# md_ver10_6.net
KiCad netlist of a schematic drawn in EAGLE
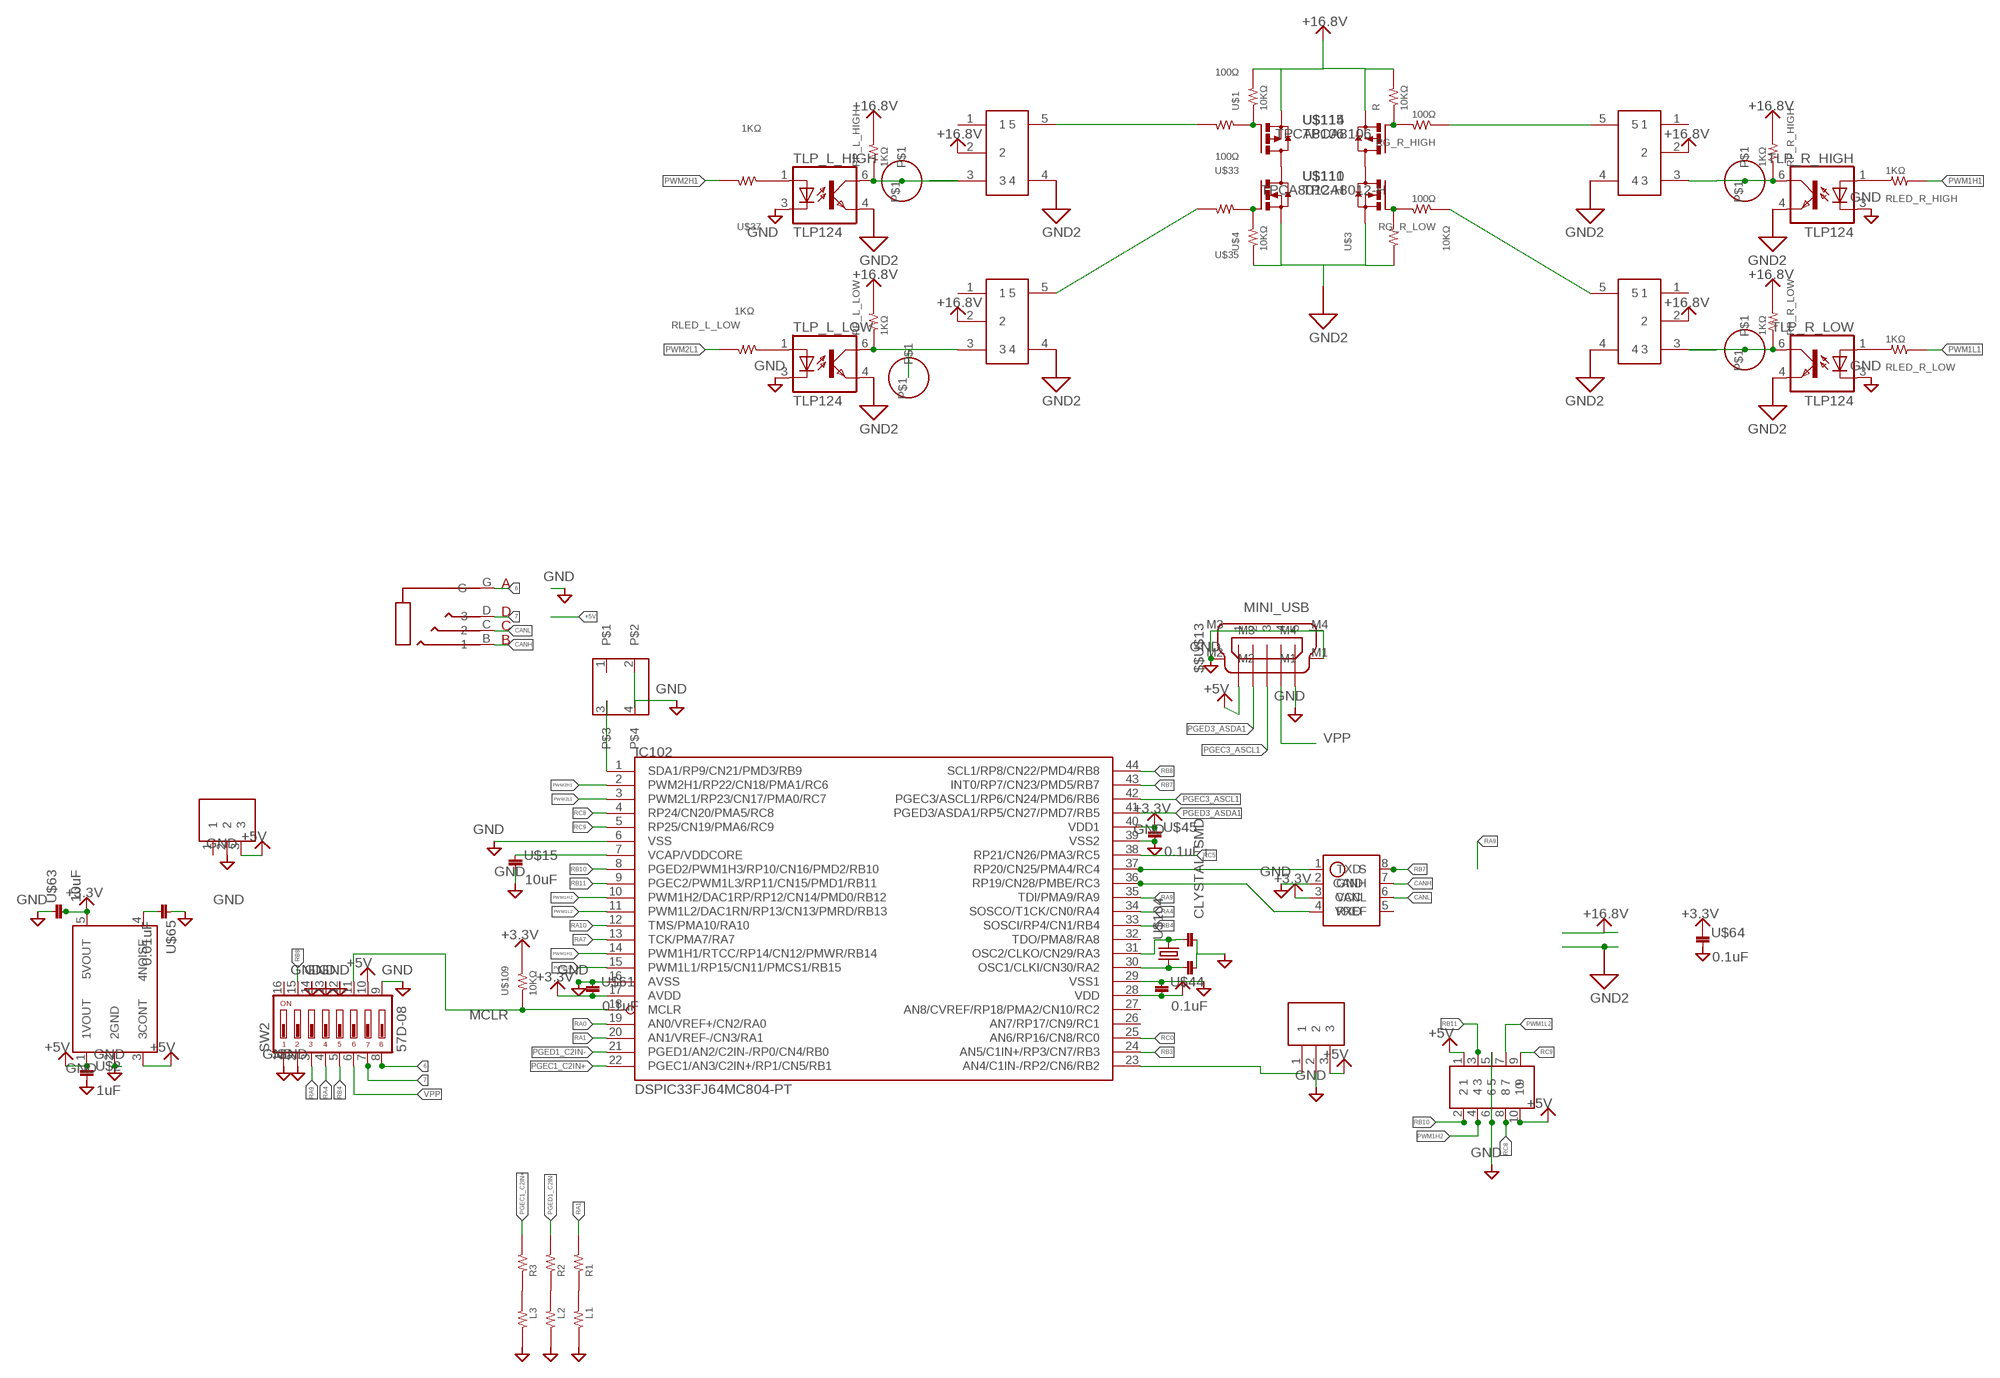
[diagram p0: schematic, sheet 1]

(export (version "E")
  (design (tool "Eeschema 10.0.6"))
  (components
    (comp (ref "$$U$5")
      (value "PAD1_4MM")
      (footprint "eagle-import:PAD1_4MM")
      (libsource (lib "eagle-import") (part "PAD1_4MM"))
    )
    (comp (ref "$$U$6")
      (value "PAD1_4MM")
      (footprint "eagle-import:PAD1_4MM")
      (libsource (lib "eagle-import") (part "PAD1_4MM"))
    )
    (comp (ref "$$U$13")
      (value "MINI_USB")
      (footprint "eagle-import:MINI_USB")
      (libsource (lib "eagle-import") (part "MINI_USB"))
    )
    (comp (ref "$$U$14")
      (value "AUDIO4")
      (footprint "eagle-import:AUDIO4_MJ")
      (libsource (lib "eagle-import") (part "AUDIO4"))
    )
    (comp (ref "$$U$102")
      (value "20pF")
      (footprint "eagle-import:1608")
      (libsource (lib "eagle-import") (part "1608"))
    )
    (comp (ref "$$U$108")
      (value "R1")
      (footprint "eagle-import:1608")
      (libsource (lib "eagle-import") (part "RESISTOR__SMD"))
    )
    (comp (ref "IC1")
      (value "Ｒ－７８Ｅ５．０")
      (footprint "eagle-import:Ｒ－７８Ｅ５．０")
      (libsource (lib "eagle-import") (part "Ｒ－７８Ｅ５．０"))
    )
    (comp (ref "IC2")
      (value "ＰＬ－ＩＲＭ")
      (footprint "eagle-import:ＰＬ－ＩＲＭ")
      (libsource (lib "eagle-import") (part "ＰＬ－ＩＲＭ"))
    )
    (comp (ref "IC100")
      (value "SN65HVD1050")
      (footprint "eagle-import:SOIC8")
      (libsource (lib "eagle-import") (part "SN65HVD1050"))
    )
    (comp (ref "IC101")
      (value "TAR5SB")
      (footprint "eagle-import:SSOP5-P-0.95")
      (libsource (lib "eagle-import") (part "TAR5SB"))
    )
    (comp (ref "IC102")
      (value "DSPIC33FJ64MC804-PT")
      (footprint "eagle-import:TQFP44")
      (libsource (lib "eagle-import") (part "DSPIC33FJ64MC804-PT"))
    )
    (comp (ref "IC_L_HIGH")
      (value "MCP1415")
      (footprint "eagle-import:SOT23-5L")
      (libsource (lib "eagle-import") (part "MCP1415"))
    )
    (comp (ref "IC_L_LOW")
      (value "MCP1415")
      (footprint "eagle-import:SOT23-5L")
      (libsource (lib "eagle-import") (part "MCP1415"))
    )
    (comp (ref "IC_R_HIGH")
      (value "MCP1415")
      (footprint "eagle-import:SOT23-5L")
      (libsource (lib "eagle-import") (part "MCP1415"))
    )
    (comp (ref "IC_R_LOW")
      (value "MCP1415")
      (footprint "eagle-import:SOT23-5L")
      (libsource (lib "eagle-import") (part "MCP1415"))
    )
    (comp (ref "R")
      (value "10KΩ")
      (footprint "eagle-import:1608")
      (libsource (lib "eagle-import") (part "RESISTOR__SMD"))
    )
    (comp (ref "RG_R_HIGH")
      (value "100Ω")
      (footprint "eagle-import:1608")
      (libsource (lib "eagle-import") (part "RESISTOR__SMD"))
    )
    (comp (ref "RG_R_LOW")
      (value "100Ω")
      (footprint "eagle-import:1608")
      (libsource (lib "eagle-import") (part "RESISTOR__SMD"))
    )
    (comp (ref "RLED_L_LOW")
      (value "1KΩ")
      (footprint "eagle-import:1608")
      (libsource (lib "eagle-import") (part "RESISTOR__SMD"))
    )
    (comp (ref "RLED_R_HIGH")
      (value "1KΩ")
      (footprint "eagle-import:1608")
      (libsource (lib "eagle-import") (part "RESISTOR__SMD"))
    )
    (comp (ref "RLED_R_LOW")
      (value "1KΩ")
      (footprint "eagle-import:1608")
      (libsource (lib "eagle-import") (part "RESISTOR__SMD"))
    )
    (comp (ref "RP_L_HIGH")
      (value "1KΩ")
      (footprint "eagle-import:1608")
      (libsource (lib "eagle-import") (part "RESISTOR__SMD"))
    )
    (comp (ref "RP_L_LOW")
      (value "1KΩ")
      (footprint "eagle-import:1608")
      (libsource (lib "eagle-import") (part "RESISTOR__SMD"))
    )
    (comp (ref "RP_R_HIGH")
      (value "1KΩ")
      (footprint "eagle-import:1608")
      (libsource (lib "eagle-import") (part "RESISTOR__SMD"))
    )
    (comp (ref "RP_R_LOW")
      (value "1KΩ")
      (footprint "eagle-import:1608")
      (libsource (lib "eagle-import") (part "RESISTOR__SMD"))
    )
    (comp (ref "SW1")
      (value "TACT")
      (footprint "eagle-import:TL1105")
      (libsource (lib "eagle-import") (part "TACT"))
    )
    (comp (ref "SW2")
      (value "57D-08")
      (footprint "eagle-import:57D")
      (libsource (lib "eagle-import") (part "57D-08"))
    )
    (comp (ref "TLP_L_HIGH")
      (value "TLP124")
      (footprint "eagle-import:11−4C1")
      (libsource (lib "eagle-import") (part "TLP124"))
    )
    (comp (ref "TLP_L_LOW")
      (value "TLP124")
      (footprint "eagle-import:11−4C1")
      (libsource (lib "eagle-import") (part "TLP124"))
    )
    (comp (ref "TLP_R_HIGH")
      (value "TLP124")
      (footprint "eagle-import:11−4C1")
      (libsource (lib "eagle-import") (part "TLP124"))
    )
    (comp (ref "TLP_R_LOW")
      (value "TLP124")
      (footprint "eagle-import:11−4C1")
      (libsource (lib "eagle-import") (part "TLP124"))
    )
    (comp (ref "U$1")
      (value "10KΩ")
      (footprint "eagle-import:1608")
      (libsource (lib "eagle-import") (part "RESISTOR__SMD"))
    )
    (comp (ref "U$2")
      (value "1uF")
      (footprint "eagle-import:1608")
      (libsource (lib "eagle-import") (part "1608"))
    )
    (comp (ref "U$3")
      (value "10KΩ")
      (footprint "eagle-import:1608")
      (libsource (lib "eagle-import") (part "RESISTOR__SMD"))
    )
    (comp (ref "U$4")
      (value "10KΩ")
      (footprint "eagle-import:1608")
      (libsource (lib "eagle-import") (part "RESISTOR__SMD"))
    )
    (comp (ref "U$7")
      (value "PAD1_4MM")
      (footprint "eagle-import:PAD1_4MM")
      (libsource (lib "eagle-import") (part "PAD1_4MM"))
    )
    (comp (ref "U$8")
      (value "PAD1_4MM")
      (footprint "eagle-import:PAD1_4MM")
      (libsource (lib "eagle-import") (part "PAD1_4MM"))
    )
    (comp (ref "U$9")
      (value "PIN_HEADER_52")
      (footprint "eagle-import:PIN_HEADER_5_2")
      (libsource (lib "eagle-import") (part "PIN_HEADER_52"))
    )
    (comp (ref "U$10")
      (value "L1")
      (footprint "eagle-import:1608")
      (libsource (lib "eagle-import") (part "RESISTOR__SMD"))
    )
    (comp (ref "U$11")
      (value "L2")
      (footprint "eagle-import:1608")
      (libsource (lib "eagle-import") (part "RESISTOR__SMD"))
    )
    (comp (ref "U$12")
      (value "L3")
      (footprint "eagle-import:1608")
      (libsource (lib "eagle-import") (part "RESISTOR__SMD"))
    )
    (comp (ref "U$15")
      (value "10uF")
      (footprint "eagle-import:2012")
      (libsource (lib "eagle-import") (part "2012"))
    )
    (comp (ref "U$33")
      (value "100Ω")
      (footprint "eagle-import:1608")
      (libsource (lib "eagle-import") (part "RESISTOR__SMD"))
    )
    (comp (ref "U$35")
      (value "100Ω")
      (footprint "eagle-import:1608")
      (libsource (lib "eagle-import") (part "RESISTOR__SMD"))
    )
    (comp (ref "U$37")
      (value "1KΩ")
      (footprint "eagle-import:1608")
      (libsource (lib "eagle-import") (part "RESISTOR__SMD"))
    )
    (comp (ref "U$44")
      (value "0.1uF")
      (footprint "eagle-import:1608")
      (libsource (lib "eagle-import") (part "1608"))
    )
    (comp (ref "U$45")
      (value "0.1uF")
      (footprint "eagle-import:1608")
      (libsource (lib "eagle-import") (part "1608"))
    )
    (comp (ref "U$61")
      (value "0.1uF")
      (footprint "eagle-import:1608")
      (libsource (lib "eagle-import") (part "1608"))
    )
    (comp (ref "U$63")
      (value "10uF")
      (footprint "eagle-import:2012")
      (libsource (lib "eagle-import") (part "2012"))
    )
    (comp (ref "U$64")
      (value "0.1uF")
      (footprint "eagle-import:1608")
      (libsource (lib "eagle-import") (part "1608"))
    )
    (comp (ref "U$65")
      (value "0.01uF")
      (footprint "eagle-import:1608")
      (libsource (lib "eagle-import") (part "1608"))
    )
    (comp (ref "U$103")
      (value "20pF")
      (footprint "eagle-import:1608")
      (libsource (lib "eagle-import") (part "1608"))
    )
    (comp (ref "U$104")
      (value "CLYSTAL_SMD")
      (footprint "eagle-import:CRYSTAL_SMD")
      (libsource (lib "eagle-import") (part "CLYSTAL_SMD"))
    )
    (comp (ref "U$106")
      (value "R3")
      (footprint "eagle-import:1608")
      (libsource (lib "eagle-import") (part "RESISTOR__SMD"))
    )
    (comp (ref "U$107")
      (value "R2")
      (footprint "eagle-import:1608")
      (libsource (lib "eagle-import") (part "RESISTOR__SMD"))
    )
    (comp (ref "U$109")
      (value "10KΩ")
      (footprint "eagle-import:1608")
      (libsource (lib "eagle-import") (part "RESISTOR__SMD"))
    )
    (comp (ref "U$110")
      (value "TPCA8012-H")
      (footprint "eagle-import:2-5Q1A")
      (libsource (lib "eagle-import") (part "TPCA8012-H"))
    )
    (comp (ref "U$111")
      (value "TPCA8012-H")
      (footprint "eagle-import:2-5Q1A")
      (libsource (lib "eagle-import") (part "TPCA8012-H"))
    )
    (comp (ref "U$114")
      (value "TPCA8106")
      (footprint "eagle-import:2-5Q1A")
      (libsource (lib "eagle-import") (part "TPCA8106"))
    )
    (comp (ref "U$115")
      (value "TPCA8106")
      (footprint "eagle-import:2-5Q1A")
      (libsource (lib "eagle-import") (part "TPCA8106"))
    )
  )
  (nets
    (net (code "1") (name "+3.3V") (class "Default")
      (node (ref "IC100") (pin "3") (pinfunction "VCC_3") (pintype "bidirectional"))
      (node (ref "IC101") (pin "5") (pinfunction "5VOUT_5") (pintype "bidirectional"))
      (node (ref "IC102") (pin "17") (pinfunction "AVDD_17") (pintype "power_in"))
      (node (ref "IC102") (pin "28") (pinfunction "VDD_28") (pintype "power_in"))
      (node (ref "IC102") (pin "40") (pinfunction "VDD1_40") (pintype "power_in"))
      (node (ref "U$109") (pin "2") (pinfunction "P$2_2") (pintype "passive"))
      (node (ref "U$44") (pin "P$2") (pinfunction "2_P$2") (pintype "passive"))
      (node (ref "U$45") (pin "P$1") (pinfunction "1_P$1") (pintype "passive"))
      (node (ref "U$61") (pin "P$2") (pinfunction "2_P$2") (pintype "passive"))
      (node (ref "U$63") (pin "2") (pinfunction "2_2") (pintype "passive"))
      (node (ref "U$64") (pin "P$1") (pinfunction "1_P$1") (pintype "passive"))
    )
    (net (code "2") (name "+5V") (class "Default")
      (node (ref "$$U$13") (pin "1") (pinfunction "1_1") (pintype "input"))
      (node (ref "IC1") (pin "3") (pinfunction "3_3") (pintype "bidirectional"))
      (node (ref "IC101") (pin "1") (pinfunction "1VOUT_1") (pintype "bidirectional"))
      (node (ref "IC101") (pin "3") (pinfunction "3CONT_3") (pintype "bidirectional"))
      (node (ref "IC2") (pin "3") (pinfunction "3_3") (pintype "bidirectional"))
      (node (ref "SW2") (pin "10") (pinfunction "10_10") (pintype "passive"))
      (node (ref "U$2") (pin "P$1") (pinfunction "1_P$1") (pintype "passive"))
      (node (ref "U$9") (pin "1") (pinfunction "1_1") (pintype "bidirectional"))
      (node (ref "U$9") (pin "10") (pinfunction "10_10") (pintype "bidirectional"))
    )
    (net (code "3") (name "+16.8V") (class "Default")
      (node (ref "IC_L_HIGH") (pin "2") (pinfunction "2_2") (pintype "bidirectional"))
      (node (ref "IC_L_LOW") (pin "2") (pinfunction "2_2") (pintype "bidirectional"))
      (node (ref "IC_R_HIGH") (pin "2") (pinfunction "2_2") (pintype "bidirectional"))
      (node (ref "IC_R_LOW") (pin "2") (pinfunction "2_2") (pintype "bidirectional"))
      (node (ref "R") (pin "2") (pinfunction "P$2_2") (pintype "passive"))
      (node (ref "RP_L_HIGH") (pin "2") (pinfunction "P$2_2") (pintype "passive"))
      (node (ref "RP_L_LOW") (pin "2") (pinfunction "P$2_2") (pintype "passive"))
      (node (ref "RP_R_HIGH") (pin "2") (pinfunction "P$2_2") (pintype "passive"))
      (node (ref "RP_R_LOW") (pin "2") (pinfunction "P$2_2") (pintype "passive"))
      (node (ref "U$1") (pin "2") (pinfunction "P$2_2") (pintype "passive"))
      (node (ref "U$114") (pin "1") (pinfunction "S_1") (pintype "passive"))
      (node (ref "U$114") (pin "2") (pinfunction "S_2") (pintype "passive"))
      (node (ref "U$114") (pin "3") (pinfunction "S_3") (pintype "passive"))
      (node (ref "U$115") (pin "1") (pinfunction "S_1") (pintype "passive"))
      (node (ref "U$115") (pin "2") (pinfunction "S_2") (pintype "passive"))
      (node (ref "U$115") (pin "3") (pinfunction "S_3") (pintype "passive"))
    )
    (net (code "4") (name "/MCLR") (class "Default")
      (node (ref "IC102") (pin "18") (pinfunction "MCLR_18") (pintype "input"))
      (node (ref "SW2") (pin "11") (pinfunction "11_11") (pintype "passive"))
      (node (ref "U$109") (pin "1") (pinfunction "P$1_1") (pintype "passive"))
    )
    (net (code "5") (name "6") (class "Default")
      (node (ref "$$U$14") (pin "G") (pinfunction "G_G") (pintype "bidirectional"))
      (node (ref "SW2") (pin "8") (pinfunction "8_8") (pintype "passive"))
    )
    (net (code "6") (name "7") (class "Default")
      (node (ref "$$U$14") (pin "D") (pinfunction "3_D") (pintype "bidirectional"))
      (node (ref "SW2") (pin "7") (pinfunction "7_7") (pintype "passive"))
    )
    (net (code "7") (name "CANH") (class "Default")
      (node (ref "$$U$14") (pin "B") (pinfunction "1_B") (pintype "bidirectional"))
      (node (ref "IC100") (pin "7") (pinfunction "CANH_7") (pintype "bidirectional"))
    )
    (net (code "8") (name "CANL") (class "Default")
      (node (ref "$$U$14") (pin "C") (pinfunction "2_C") (pintype "bidirectional"))
      (node (ref "IC100") (pin "6") (pinfunction "CANL_6") (pintype "bidirectional"))
    )
    (net (code "9") (name "GND") (class "Default")
      (node (ref "$$U$102") (pin "P$2") (pinfunction "2_P$2") (pintype "passive"))
      (node (ref "$$U$13") (pin "5") (pinfunction "5_5") (pintype "input"))
      (node (ref "$$U$13") (pin "M1") (pinfunction "M1_M1") (pintype "bidirectional"))
      (node (ref "$$U$13") (pin "M2") (pinfunction "M2_M2") (pintype "bidirectional"))
      (node (ref "$$U$13") (pin "M3") (pinfunction "M3_M3") (pintype "bidirectional"))
      (node (ref "$$U$13") (pin "M4") (pinfunction "M4_M4") (pintype "bidirectional"))
      (node (ref "IC1") (pin "2") (pinfunction "2_2") (pintype "bidirectional"))
      (node (ref "IC100") (pin "2") (pinfunction "GND_2") (pintype "bidirectional"))
      (node (ref "IC101") (pin "2") (pinfunction "2GND_2") (pintype "bidirectional"))
      (node (ref "IC102") (pin "16") (pinfunction "AVSS_16") (pintype "power_in"))
      (node (ref "IC102") (pin "29") (pinfunction "VSS1_29") (pintype "power_in"))
      (node (ref "IC102") (pin "39") (pinfunction "VSS2_39") (pintype "power_in"))
      (node (ref "IC102") (pin "6") (pinfunction "VSS_6") (pintype "power_in"))
      (node (ref "IC2") (pin "2") (pinfunction "2_2") (pintype "bidirectional"))
      (node (ref "SW1") (pin "2") (pinfunction "P$2_2") (pintype "bidirectional"))
      (node (ref "SW1") (pin "4") (pinfunction "P$4_4") (pintype "bidirectional"))
      (node (ref "SW2") (pin "1") (pinfunction "1_1") (pintype "passive"))
      (node (ref "SW2") (pin "12") (pinfunction "12_12") (pintype "passive"))
      (node (ref "SW2") (pin "13") (pinfunction "13_13") (pintype "passive"))
      (node (ref "SW2") (pin "14") (pinfunction "14_14") (pintype "passive"))
      (node (ref "SW2") (pin "2") (pinfunction "2_2") (pintype "passive"))
      (node (ref "SW2") (pin "9") (pinfunction "9_9") (pintype "passive"))
      (node (ref "TLP_L_HIGH") (pin "3") (pinfunction "C_3") (pintype "passive"))
      (node (ref "TLP_L_LOW") (pin "3") (pinfunction "C_3") (pintype "passive"))
      (node (ref "TLP_R_HIGH") (pin "3") (pinfunction "C_3") (pintype "passive"))
      (node (ref "TLP_R_LOW") (pin "3") (pinfunction "C_3") (pintype "passive"))
      (node (ref "U$10") (pin "1") (pinfunction "P$1_1") (pintype "passive"))
      (node (ref "U$103") (pin "P$2") (pinfunction "2_P$2") (pintype "passive"))
      (node (ref "U$11") (pin "1") (pinfunction "P$1_1") (pintype "passive"))
      (node (ref "U$12") (pin "1") (pinfunction "P$1_1") (pintype "passive"))
      (node (ref "U$15") (pin "2") (pinfunction "2_2") (pintype "passive"))
      (node (ref "U$2") (pin "P$2") (pinfunction "2_P$2") (pintype "passive"))
      (node (ref "U$44") (pin "P$1") (pinfunction "1_P$1") (pintype "passive"))
      (node (ref "U$45") (pin "P$2") (pinfunction "2_P$2") (pintype "passive"))
      (node (ref "U$61") (pin "P$1") (pinfunction "1_P$1") (pintype "passive"))
      (node (ref "U$63") (pin "1") (pinfunction "1_1") (pintype "passive"))
      (node (ref "U$64") (pin "P$2") (pinfunction "2_P$2") (pintype "passive"))
      (node (ref "U$65") (pin "P$1") (pinfunction "1_P$1") (pintype "passive"))
      (node (ref "U$9") (pin "5") (pinfunction "5_5") (pintype "bidirectional"))
      (node (ref "U$9") (pin "6") (pinfunction "6_6") (pintype "bidirectional"))
    )
    (net (code "10") (name "GND2") (class "Default")
      (node (ref "IC_L_HIGH") (pin "4") (pinfunction "4_4") (pintype "bidirectional"))
      (node (ref "IC_L_LOW") (pin "4") (pinfunction "4_4") (pintype "bidirectional"))
      (node (ref "IC_R_HIGH") (pin "4") (pinfunction "4_4") (pintype "bidirectional"))
      (node (ref "IC_R_LOW") (pin "4") (pinfunction "4_4") (pintype "bidirectional"))
      (node (ref "TLP_L_HIGH") (pin "4") (pinfunction "EMIT_4") (pintype "passive"))
      (node (ref "TLP_L_LOW") (pin "4") (pinfunction "EMIT_4") (pintype "passive"))
      (node (ref "TLP_R_HIGH") (pin "4") (pinfunction "EMIT_4") (pintype "passive"))
      (node (ref "TLP_R_LOW") (pin "4") (pinfunction "EMIT_4") (pintype "passive"))
      (node (ref "U$110") (pin "1") (pinfunction "S_1") (pintype "passive"))
      (node (ref "U$110") (pin "2") (pinfunction "S_2") (pintype "passive"))
      (node (ref "U$110") (pin "3") (pinfunction "S_3") (pintype "passive"))
      (node (ref "U$111") (pin "1") (pinfunction "S_1") (pintype "passive"))
      (node (ref "U$111") (pin "2") (pinfunction "S_2") (pintype "passive"))
      (node (ref "U$111") (pin "3") (pinfunction "S_3") (pintype "passive"))
      (node (ref "U$3") (pin "1") (pinfunction "P$1_1") (pintype "passive"))
      (node (ref "U$4") (pin "1") (pinfunction "P$1_1") (pintype "passive"))
    )
    (net (code "11") (name "Net-($$U$102-1)") (class "Default")
      (node (ref "$$U$102") (pin "P$1") (pinfunction "1_P$1") (pintype "passive"))
      (node (ref "IC102") (pin "30") (pinfunction "OSC1/CLKI/CN30/RA2_30") (pintype "bidirectional"))
      (node (ref "U$104") (pin "1") (pinfunction "1_1") (pintype "passive"))
    )
    (net (code "12") (name "Net-($$U$108-P$1)") (class "Default")
      (node (ref "$$U$108") (pin "1") (pinfunction "P$1_1") (pintype "passive"))
      (node (ref "U$10") (pin "2") (pinfunction "P$2_2") (pintype "passive"))
    )
    (net (code "13") (name "Net-(IC100-RXD)") (class "Default")
      (node (ref "IC100") (pin "4") (pinfunction "RXD_4") (pintype "bidirectional"))
      (node (ref "IC102") (pin "36") (pinfunction "RP19/CN28/PMBE/RC3_36") (pintype "bidirectional"))
    )
    (net (code "14") (name "Net-(IC100-TXD)") (class "Default")
      (node (ref "IC100") (pin "1") (pinfunction "TXD_1") (pintype "bidirectional"))
      (node (ref "IC102") (pin "37") (pinfunction "RP20/CN25/PMA4/RC4_37") (pintype "bidirectional"))
    )
    (net (code "15") (name "Net-(IC101-4NOISE)") (class "Default")
      (node (ref "IC101") (pin "4") (pinfunction "4NOISE_4") (pintype "bidirectional"))
      (node (ref "U$65") (pin "P$2") (pinfunction "2_P$2") (pintype "passive"))
    )
    (net (code "16") (name "Net-(IC102-AN4{slash}C1IN-{slash}RP2{slash}CN6{slash}RB2)") (class "Default")
      (node (ref "IC102") (pin "23") (pinfunction "AN4/C1IN-/RP2/CN6/RB2_23") (pintype "bidirectional"))
      (node (ref "IC2") (pin "1") (pinfunction "1_1") (pintype "bidirectional"))
    )
    (net (code "17") (name "Net-(IC102-OSC2{slash}CLKO{slash}CN29{slash}RA3)") (class "Default")
      (node (ref "IC102") (pin "31") (pinfunction "OSC2/CLKO/CN29/RA3_31") (pintype "bidirectional"))
      (node (ref "U$103") (pin "P$1") (pinfunction "1_P$1") (pintype "passive"))
      (node (ref "U$104") (pin "2") (pinfunction "2_2") (pintype "passive"))
    )
    (net (code "18") (name "Net-(IC102-SDA1{slash}RP9{slash}CN21{slash}PMD3{slash}RB9)") (class "Default")
      (node (ref "IC102") (pin "1") (pinfunction "SDA1/RP9/CN21/PMD3/RB9_1") (pintype "bidirectional"))
      (node (ref "SW1") (pin "3") (pinfunction "P$3_3") (pintype "bidirectional"))
    )
    (net (code "19") (name "Net-(IC102-VCAP{slash}VDDCORE)") (class "Default")
      (node (ref "IC102") (pin "7") (pinfunction "VCAP/VDDCORE_7") (pintype "power_in"))
      (node (ref "U$15") (pin "1") (pinfunction "1_1") (pintype "passive"))
    )
    (net (code "20") (name "Net-(R-P$1)") (class "Default")
      (node (ref "R") (pin "1") (pinfunction "P$1_1") (pintype "passive"))
      (node (ref "RG_R_HIGH") (pin "2") (pinfunction "P$2_2") (pintype "passive"))
      (node (ref "U$114") (pin "4") (pinfunction "G_4") (pintype "passive"))
    )
    (net (code "21") (name "Net-(RG_R_HIGH-P$1)") (class "Default")
      (node (ref "IC_R_HIGH") (pin "5") (pinfunction "5_5") (pintype "bidirectional"))
      (node (ref "RG_R_HIGH") (pin "1") (pinfunction "P$1_1") (pintype "passive"))
    )
    (net (code "22") (name "Net-(RG_R_LOW-P$1)") (class "Default")
      (node (ref "IC_R_LOW") (pin "5") (pinfunction "5_5") (pintype "bidirectional"))
      (node (ref "RG_R_LOW") (pin "1") (pinfunction "P$1_1") (pintype "passive"))
    )
    (net (code "23") (name "Net-(RG_R_LOW-P$2)") (class "Default")
      (node (ref "RG_R_LOW") (pin "2") (pinfunction "P$2_2") (pintype "passive"))
      (node (ref "U$110") (pin "4") (pinfunction "G_4") (pintype "passive"))
      (node (ref "U$3") (pin "2") (pinfunction "P$2_2") (pintype "passive"))
    )
    (net (code "24") (name "Net-(RLED_L_LOW-P$1)") (class "Default")
      (node (ref "RLED_L_LOW") (pin "1") (pinfunction "P$1_1") (pintype "passive"))
      (node (ref "TLP_L_LOW") (pin "1") (pinfunction "A_1") (pintype "passive"))
    )
    (net (code "25") (name "Net-(RLED_R_HIGH-P$1)") (class "Default")
      (node (ref "RLED_R_HIGH") (pin "1") (pinfunction "P$1_1") (pintype "passive"))
      (node (ref "TLP_R_HIGH") (pin "1") (pinfunction "A_1") (pintype "passive"))
    )
    (net (code "26") (name "Net-(RLED_R_LOW-P$1)") (class "Default")
      (node (ref "RLED_R_LOW") (pin "1") (pinfunction "P$1_1") (pintype "passive"))
      (node (ref "TLP_R_LOW") (pin "1") (pinfunction "A_1") (pintype "passive"))
    )
    (net (code "27") (name "Net-(RP_L_HIGH-P$1)") (class "Default")
      (node (ref "$$U$5") (pin "P$1") (pinfunction "P$1_P$1") (pintype "bidirectional"))
      (node (ref "IC_L_HIGH") (pin "3") (pinfunction "3_3") (pintype "bidirectional"))
      (node (ref "RP_L_HIGH") (pin "1") (pinfunction "P$1_1") (pintype "passive"))
      (node (ref "TLP_L_HIGH") (pin "6") (pinfunction "COL_6") (pintype "passive"))
    )
    (net (code "28") (name "Net-(RP_L_LOW-P$1)") (class "Default")
      (node (ref "$$U$6") (pin "P$1") (pinfunction "P$1_P$1") (pintype "bidirectional"))
      (node (ref "IC_L_LOW") (pin "3") (pinfunction "3_3") (pintype "bidirectional"))
      (node (ref "RP_L_LOW") (pin "1") (pinfunction "P$1_1") (pintype "passive"))
      (node (ref "TLP_L_LOW") (pin "6") (pinfunction "COL_6") (pintype "passive"))
    )
    (net (code "29") (name "Net-(RP_R_HIGH-P$1)") (class "Default")
      (node (ref "IC_R_HIGH") (pin "3") (pinfunction "3_3") (pintype "bidirectional"))
      (node (ref "RP_R_HIGH") (pin "1") (pinfunction "P$1_1") (pintype "passive"))
      (node (ref "TLP_R_HIGH") (pin "6") (pinfunction "COL_6") (pintype "passive"))
      (node (ref "U$8") (pin "P$1") (pinfunction "P$1_P$1") (pintype "bidirectional"))
    )
    (net (code "30") (name "Net-(RP_R_LOW-P$1)") (class "Default")
      (node (ref "IC_R_LOW") (pin "3") (pinfunction "3_3") (pintype "bidirectional"))
      (node (ref "RP_R_LOW") (pin "1") (pinfunction "P$1_1") (pintype "passive"))
      (node (ref "TLP_R_LOW") (pin "6") (pinfunction "COL_6") (pintype "passive"))
      (node (ref "U$7") (pin "P$1") (pinfunction "P$1_P$1") (pintype "bidirectional"))
    )
    (net (code "31") (name "Net-(TLP_L_HIGH-A)") (class "Default")
      (node (ref "TLP_L_HIGH") (pin "1") (pinfunction "A_1") (pintype "passive"))
      (node (ref "U$37") (pin "1") (pinfunction "P$1_1") (pintype "passive"))
    )
    (net (code "32") (name "Net-(U$1-P$1)") (class "Default")
      (node (ref "U$1") (pin "1") (pinfunction "P$1_1") (pintype "passive"))
      (node (ref "U$115") (pin "4") (pinfunction "G_4") (pintype "passive"))
      (node (ref "U$33") (pin "1") (pinfunction "P$1_1") (pintype "passive"))
    )
    (net (code "33") (name "Net-(U$33-P$2)") (class "Default")
      (node (ref "IC_L_HIGH") (pin "5") (pinfunction "5_5") (pintype "bidirectional"))
      (node (ref "U$33") (pin "2") (pinfunction "P$2_2") (pintype "passive"))
    )
    (net (code "34") (name "Net-(U$35-P$2)") (class "Default")
      (node (ref "IC_L_LOW") (pin "5") (pinfunction "5_5") (pintype "bidirectional"))
      (node (ref "U$35") (pin "2") (pinfunction "P$2_2") (pintype "passive"))
    )
    (net (code "35") (name "Net-(U$106-P$1)") (class "Default")
      (node (ref "U$106") (pin "1") (pinfunction "P$1_1") (pintype "passive"))
      (node (ref "U$12") (pin "2") (pinfunction "P$2_2") (pintype "passive"))
    )
    (net (code "36") (name "Net-(U$107-P$1)") (class "Default")
      (node (ref "U$107") (pin "1") (pinfunction "P$1_1") (pintype "passive"))
      (node (ref "U$11") (pin "2") (pinfunction "P$2_2") (pintype "passive"))
    )
    (net (code "37") (name "Net-(U$110-D-Pad5)") (class "Default")
      (node (ref "U$110") (pin "5") (pinfunction "D_5") (pintype "passive"))
      (node (ref "U$110") (pin "6") (pinfunction "D_6") (pintype "passive"))
      (node (ref "U$110") (pin "7") (pinfunction "D_7") (pintype "passive"))
      (node (ref "U$110") (pin "8") (pinfunction "D_8") (pintype "passive"))
      (node (ref "U$114") (pin "5") (pinfunction "D_5") (pintype "passive"))
      (node (ref "U$114") (pin "6") (pinfunction "D_6") (pintype "passive"))
      (node (ref "U$114") (pin "7") (pinfunction "D_7") (pintype "passive"))
      (node (ref "U$114") (pin "8") (pinfunction "D_8") (pintype "passive"))
    )
    (net (code "38") (name "Net-(U$111-D-Pad5)") (class "Default")
      (node (ref "U$111") (pin "5") (pinfunction "D_5") (pintype "passive"))
      (node (ref "U$111") (pin "6") (pinfunction "D_6") (pintype "passive"))
      (node (ref "U$111") (pin "7") (pinfunction "D_7") (pintype "passive"))
      (node (ref "U$111") (pin "8") (pinfunction "D_8") (pintype "passive"))
      (node (ref "U$115") (pin "5") (pinfunction "D_5") (pintype "passive"))
      (node (ref "U$115") (pin "6") (pinfunction "D_6") (pintype "passive"))
      (node (ref "U$115") (pin "7") (pinfunction "D_7") (pintype "passive"))
      (node (ref "U$115") (pin "8") (pinfunction "D_8") (pintype "passive"))
    )
    (net (code "39") (name "Net-(U$111-G)") (class "Default")
      (node (ref "U$111") (pin "4") (pinfunction "G_4") (pintype "passive"))
      (node (ref "U$35") (pin "1") (pinfunction "P$1_1") (pintype "passive"))
      (node (ref "U$4") (pin "2") (pinfunction "P$2_2") (pintype "passive"))
    )
    (net (code "40") (name "PGEC1_C2IN+") (class "Default")
      (node (ref "IC102") (pin "22") (pinfunction "PGEC1/AN3/C2IN+/RP1/CN5/RB1_22") (pintype "bidirectional"))
      (node (ref "U$106") (pin "2") (pinfunction "P$2_2") (pintype "passive"))
    )
    (net (code "41") (name "PGEC3_ASCL1") (class "Default")
      (node (ref "$$U$13") (pin "3") (pinfunction "3_3") (pintype "input"))
      (node (ref "IC102") (pin "42") (pinfunction "PGEC3/ASCL1/RP6/CN24/PMD6/RB6_42") (pintype "bidirectional"))
    )
    (net (code "42") (name "PGED1_C2IN-") (class "Default")
      (node (ref "IC102") (pin "21") (pinfunction "PGED1/AN2/C2IN-/RP0/CN4/RB0_21") (pintype "bidirectional"))
      (node (ref "U$107") (pin "2") (pinfunction "P$2_2") (pintype "passive"))
    )
    (net (code "43") (name "PGED3_ASDA1") (class "Default")
      (node (ref "$$U$13") (pin "2") (pinfunction "2_2") (pintype "input"))
      (node (ref "IC102") (pin "41") (pinfunction "PGED3/ASDA1/RP5/CN27/PMD7/RB5_41") (pintype "bidirectional"))
    )
    (net (code "44") (name "PWM1H1") (class "Default")
      (node (ref "IC102") (pin "14") (pinfunction "PWM1H1/RTCC/RP14/CN12/PMWR/RB14_14") (pintype "bidirectional"))
      (node (ref "RLED_R_HIGH") (pin "2") (pinfunction "P$2_2") (pintype "passive"))
    )
    (net (code "45") (name "PWM1H2") (class "Default")
      (node (ref "IC102") (pin "10") (pinfunction "PWM1H2/DAC1RP/RP12/CN14/PMD0/RB12_10") (pintype "bidirectional"))
      (node (ref "U$9") (pin "4") (pinfunction "4_4") (pintype "bidirectional"))
    )
    (net (code "46") (name "PWM1L1") (class "Default")
      (node (ref "IC102") (pin "15") (pinfunction "PWM1L1/RP15/CN11/PMCS1/RB15_15") (pintype "bidirectional"))
      (node (ref "RLED_R_LOW") (pin "2") (pinfunction "P$2_2") (pintype "passive"))
    )
    (net (code "47") (name "PWM1L2") (class "Default")
      (node (ref "IC102") (pin "11") (pinfunction "PWM1L2/DAC1RN/RP13/CN13/PMRD/RB13_11") (pintype "bidirectional"))
      (node (ref "U$9") (pin "7") (pinfunction "7_7") (pintype "bidirectional"))
    )
    (net (code "48") (name "PWM2H1") (class "Default")
      (node (ref "IC102") (pin "2") (pinfunction "PWM2H1/RP22/CN18/PMA1/RC6_2") (pintype "bidirectional"))
      (node (ref "U$37") (pin "2") (pinfunction "P$2_2") (pintype "passive"))
    )
    (net (code "49") (name "PWM2L1") (class "Default")
      (node (ref "IC102") (pin "3") (pinfunction "PWM2L1/RP23/CN17/PMA0/RC7_3") (pintype "bidirectional"))
      (node (ref "RLED_L_LOW") (pin "2") (pinfunction "P$2_2") (pintype "passive"))
    )
    (net (code "50") (name "RA0") (class "Default")
      (node (ref "IC102") (pin "19") (pinfunction "AN0/VREF+/CN2/RA0_19") (pintype "bidirectional"))
    )
    (net (code "51") (name "RA1") (class "Default")
      (node (ref "$$U$108") (pin "2") (pinfunction "P$2_2") (pintype "passive"))
      (node (ref "IC102") (pin "20") (pinfunction "AN1/VREF-/CN3/RA1_20") (pintype "bidirectional"))
    )
    (net (code "52") (name "RA4") (class "Default")
      (node (ref "IC102") (pin "34") (pinfunction "SOSCO/T1CK/CN0/RA4_34") (pintype "bidirectional"))
      (node (ref "SW2") (pin "4") (pinfunction "4_4") (pintype "passive"))
    )
    (net (code "53") (name "RA7") (class "Default")
      (node (ref "IC102") (pin "13") (pinfunction "TCK/PMA7/RA7_13") (pintype "bidirectional"))
    )
    (net (code "54") (name "RA9") (class "Default")
      (node (ref "IC102") (pin "35") (pinfunction "TDI/PMA9/RA9_35") (pintype "bidirectional"))
      (node (ref "SW2") (pin "3") (pinfunction "3_3") (pintype "passive"))
    )
    (net (code "55") (name "RA10") (class "Default")
      (node (ref "IC102") (pin "12") (pinfunction "TMS/PMA10/RA10_12") (pintype "bidirectional"))
    )
    (net (code "56") (name "RB3") (class "Default")
      (node (ref "IC102") (pin "24") (pinfunction "AN5/C1IN+/RP3/CN7/RB3_24") (pintype "bidirectional"))
    )
    (net (code "57") (name "RB4") (class "Default")
      (node (ref "IC102") (pin "33") (pinfunction "SOSCI/RP4/CN1/RB4_33") (pintype "bidirectional"))
      (node (ref "SW2") (pin "5") (pinfunction "5_5") (pintype "passive"))
    )
    (net (code "58") (name "RB7") (class "Default")
      (node (ref "IC100") (pin "8") (pinfunction "S_8") (pintype "bidirectional"))
      (node (ref "IC102") (pin "43") (pinfunction "INT0/RP7/CN23/PMD5/RB7_43") (pintype "bidirectional"))
    )
    (net (code "59") (name "RB8") (class "Default")
      (node (ref "IC102") (pin "44") (pinfunction "SCL1/RP8/CN22/PMD4/RB8_44") (pintype "bidirectional"))
      (node (ref "SW2") (pin "15") (pinfunction "15_15") (pintype "passive"))
    )
    (net (code "60") (name "RB10") (class "Default")
      (node (ref "IC102") (pin "8") (pinfunction "PGED2/PWM1H3/RP10/CN16/PMD2/RB10_8") (pintype "bidirectional"))
      (node (ref "U$9") (pin "2") (pinfunction "2_2") (pintype "bidirectional"))
    )
    (net (code "61") (name "RB11") (class "Default")
      (node (ref "IC102") (pin "9") (pinfunction "PGEC2/PWM1L3/RP11/CN15/PMD1/RB11_9") (pintype "bidirectional"))
      (node (ref "U$9") (pin "3") (pinfunction "3_3") (pintype "bidirectional"))
    )
    (net (code "62") (name "RC0") (class "Default")
      (node (ref "IC102") (pin "25") (pinfunction "AN6/RP16/CN8/RC0_25") (pintype "bidirectional"))
    )
    (net (code "63") (name "RC5") (class "Default")
      (node (ref "IC102") (pin "38") (pinfunction "RP21/CN26/PMA3/RC5_38") (pintype "bidirectional"))
    )
    (net (code "64") (name "RC8") (class "Default")
      (node (ref "IC102") (pin "4") (pinfunction "RP24/CN20/PMA5/RC8_4") (pintype "bidirectional"))
      (node (ref "U$9") (pin "8") (pinfunction "8_8") (pintype "bidirectional"))
    )
    (net (code "65") (name "RC9") (class "Default")
      (node (ref "IC102") (pin "5") (pinfunction "RP25/CN19/PMA6/RC9_5") (pintype "bidirectional"))
      (node (ref "U$9") (pin "9") (pinfunction "9_9") (pintype "bidirectional"))
    )
    (net (code "66") (name "VPP") (class "Default")
      (node (ref "$$U$13") (pin "4") (pinfunction "4_4") (pintype "input"))
      (node (ref "SW2") (pin "6") (pinfunction "6_6") (pintype "passive"))
    )
    (net (code "67") (name "unconnected-(IC1-Pad1)") (class "Default")
      (node (ref "IC1") (pin "1") (pinfunction "1_1") (pintype "bidirectional"))
    )
    (net (code "68") (name "unconnected-(IC100-VREF-Pad5)") (class "Default")
      (node (ref "IC100") (pin "5") (pinfunction "VREF_5") (pintype "bidirectional"))
    )
    (net (code "69") (name "unconnected-(IC102-AN7{slash}RP17{slash}CN9{slash}RC1-Pad26)") (class "Default")
      (node (ref "IC102") (pin "26") (pinfunction "AN7/RP17/CN9/RC1_26") (pintype "bidirectional"))
    )
    (net (code "70") (name "unconnected-(IC102-AN8{slash}CVREF{slash}RP18{slash}PMA2{slash}CN10{slash}RC2-Pad27)") (class "Default")
      (node (ref "IC102") (pin "27") (pinfunction "AN8/CVREF/RP18/PMA2/CN10/RC2_27") (pintype "bidirectional"))
    )
    (net (code "71") (name "unconnected-(IC102-TDO{slash}PMA8{slash}RA8-Pad32)") (class "Default")
      (node (ref "IC102") (pin "32") (pinfunction "TDO/PMA8/RA8_32") (pintype "bidirectional"))
    )
    (net (code "72") (name "unconnected-(IC_L_HIGH-Pad1)") (class "Default")
      (node (ref "IC_L_HIGH") (pin "1") (pinfunction "1_1") (pintype "bidirectional"))
    )
    (net (code "73") (name "unconnected-(IC_L_LOW-Pad1)") (class "Default")
      (node (ref "IC_L_LOW") (pin "1") (pinfunction "1_1") (pintype "bidirectional"))
    )
    (net (code "74") (name "unconnected-(IC_R_HIGH-Pad1)") (class "Default")
      (node (ref "IC_R_HIGH") (pin "1") (pinfunction "1_1") (pintype "bidirectional"))
    )
    (net (code "75") (name "unconnected-(IC_R_LOW-Pad1)") (class "Default")
      (node (ref "IC_R_LOW") (pin "1") (pinfunction "1_1") (pintype "bidirectional"))
    )
    (net (code "76") (name "unconnected-(SW1-P$1-Pad1)") (class "Default")
      (node (ref "SW1") (pin "1") (pinfunction "P$1_1") (pintype "bidirectional"))
    )
    (net (code "77") (name "unconnected-(SW2-Pad16)") (class "Default")
      (node (ref "SW2") (pin "16") (pinfunction "16_16") (pintype "passive"))
    )
  )
)
